# SCH_ESP-CellCore_USB_Interlock_RevA3_2.net
KiCad netlist of a schematic drawn in EasyEDA
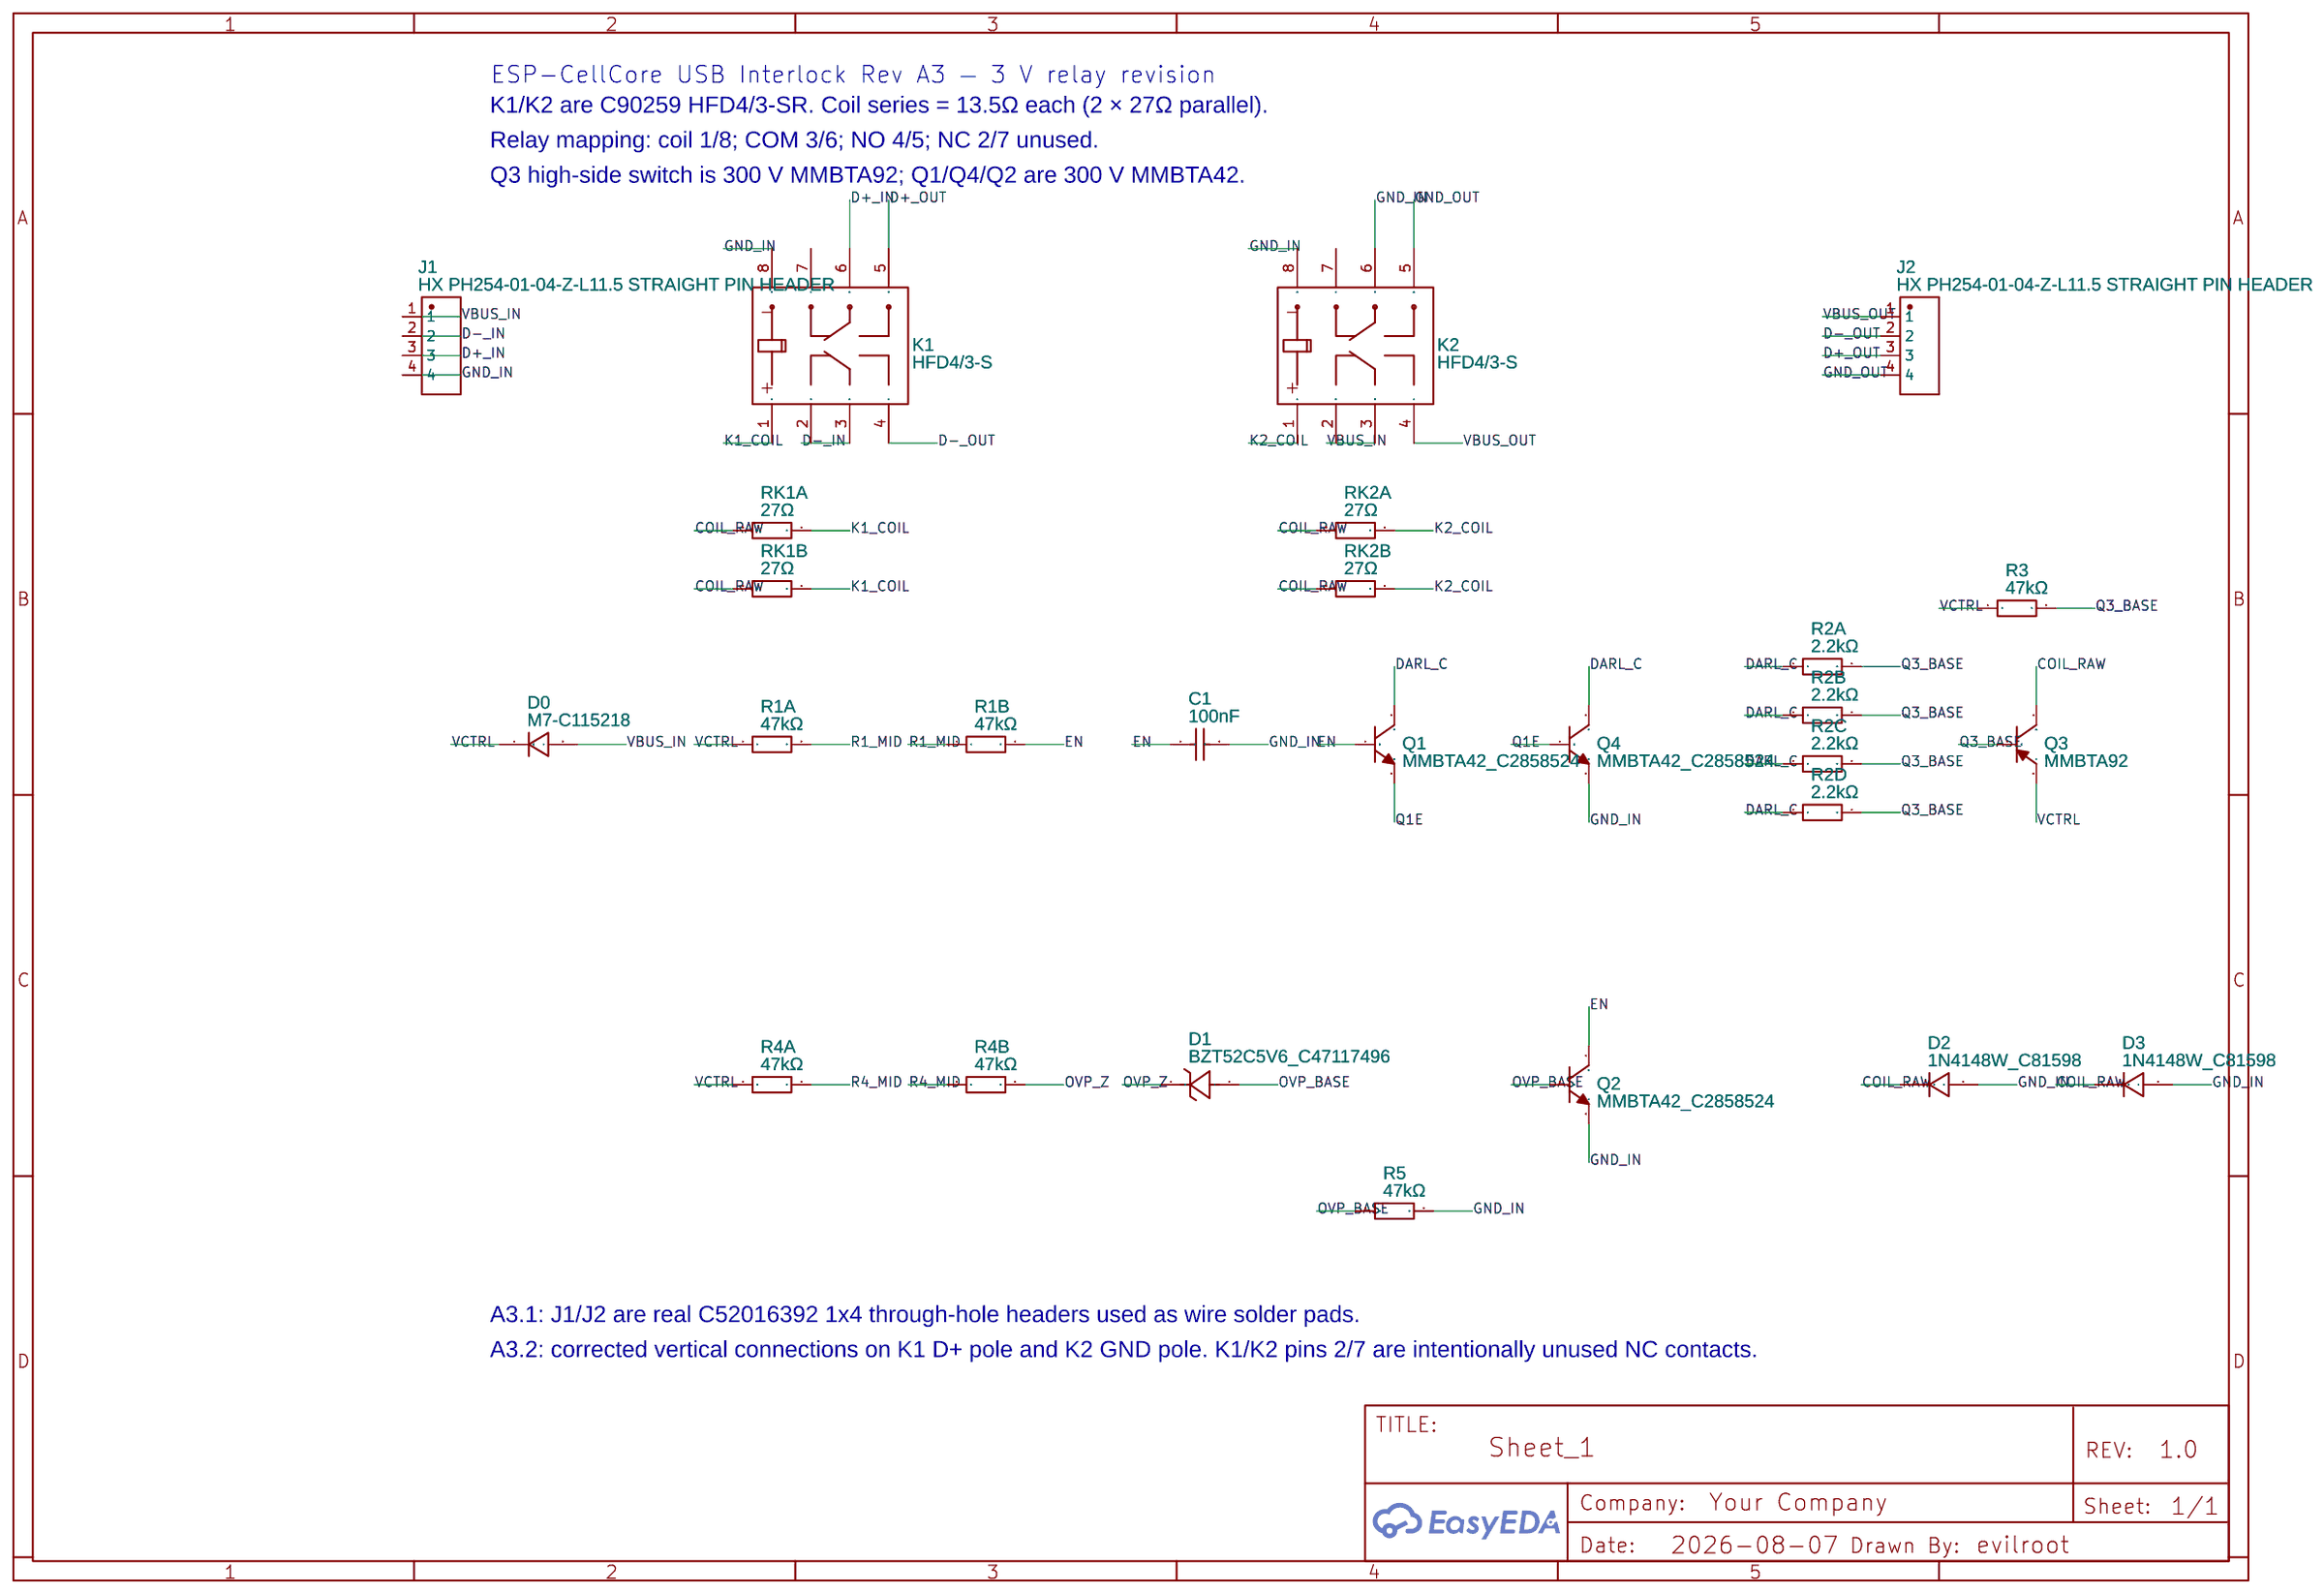
[diagram p0: schematic sheet]

(export (version "E")
  (design (tool "Eeschema 10.0.6"))
  (components
    (comp (ref "C1")
      (value "100nF")
      (fields
        (field (name "Manufacturer Part") "C0805C104K5RAC7800")
        (field (name "Manufacturer") "KEMET(基美)")
      )
      (libsource (lib "") (part "C0805C104K5RACTU"))
    )
    (comp (ref "D0")
      (value "M7-C115218")
      (fields (field (name "Manufacturer Part") "M7") (field (name "Manufacturer") "晶导微电子"))
      (libsource (lib "") (part "M7-C115218"))
    )
    (comp (ref "D1")
      (value "BZT52C5V6_C47117496")
      (fields (field (name "Manufacturer Part") "BZT52C5V6") (field (name "Manufacturer") "baocheng(宝乘)"))
      (libsource (lib "") (part "BZT52C5V6_C47117496"))
    )
    (comp (ref "D2")
      (value "1N4148W_C81598")
      (fields (field (name "Manufacturer Part") "1N4148W") (field (name "Manufacturer") "ST(先科)"))
      (libsource (lib "") (part "1N4148W_C81598"))
    )
    (comp (ref "D3")
      (value "1N4148W_C81598")
      (fields (field (name "Manufacturer Part") "1N4148W") (field (name "Manufacturer") "ST(先科)"))
      (libsource (lib "") (part "1N4148W_C81598"))
    )
    (comp (ref "J1")
      (value "HX PH254-01-04-Z-L11.5 STRAIGHT PIN HEADER")
      (fields
        (field (name "Manufacturer Part") "HX PH254-01-04-Z-L11.5 straight pin header")
        (field (name "Manufacturer") "hanxia(韩下)")
      )
      (libsource (lib "") (part "HX PH254-01-04-Z-L11.5 STRAIGHT PIN HEADER"))
    )
    (comp (ref "J2")
      (value "HX PH254-01-04-Z-L11.5 STRAIGHT PIN HEADER")
      (fields
        (field (name "Manufacturer Part") "HX PH254-01-04-Z-L11.5 straight pin header")
        (field (name "Manufacturer") "hanxia(韩下)")
      )
      (libsource (lib "") (part "HX PH254-01-04-Z-L11.5 STRAIGHT PIN HEADER"))
    )
    (comp (ref "K1")
      (value "HFD4/3-S")
      (fields (field (name "Manufacturer Part") "HFD4/3-SR") (field (name "Manufacturer") "HF(宏发)"))
      (libsource (lib "") (part "HFD4/3-S"))
    )
    (comp (ref "K2")
      (value "HFD4/3-S")
      (fields (field (name "Manufacturer Part") "HFD4/3-SR") (field (name "Manufacturer") "HF(宏发)"))
      (libsource (lib "") (part "HFD4/3-S"))
    )
    (comp (ref "Q1")
      (value "MMBTA42_C2858524")
      (fields (field (name "Manufacturer Part") "MMBTA42") (field (name "Manufacturer") "MDD(辰达半导体)"))
      (libsource (lib "") (part "MMBTA42_C2858524"))
    )
    (comp (ref "Q2")
      (value "MMBTA42_C2858524")
      (fields (field (name "Manufacturer Part") "MMBTA42") (field (name "Manufacturer") "MDD(辰达半导体)"))
      (libsource (lib "") (part "MMBTA42_C2858524"))
    )
    (comp (ref "Q3")
      (value "MMBTA92")
      (fields (field (name "Manufacturer") "GOODWORK(固得沃克)"))
      (libsource (lib "") (part "MMBTA92"))
    )
    (comp (ref "Q4")
      (value "MMBTA42_C2858524")
      (fields (field (name "Manufacturer Part") "MMBTA42") (field (name "Manufacturer") "MDD(辰达半导体)"))
      (libsource (lib "") (part "MMBTA42_C2858524"))
    )
    (comp (ref "R1A")
      (value "47kΩ")
      (fields (field (name "Manufacturer Part") "AC0805FR-0747KL") (field (name "Manufacturer") "YAGEO(国巨)"))
      (libsource (lib "") (part "AC0805FR-0747KL_4"))
    )
    (comp (ref "R1B")
      (value "47kΩ")
      (fields (field (name "Manufacturer Part") "AC0805FR-0747KL") (field (name "Manufacturer") "YAGEO(国巨)"))
      (libsource (lib "") (part "AC0805FR-0747KL"))
    )
    (comp (ref "R2A")
      (value "2.2kΩ")
      (fields
        (field (name "Manufacturer Part") "0805W8F2201T5E")
        (field (name "Manufacturer") "UNI-ROYAL(厚声)")
      )
      (libsource (lib "") (part "0805W8F2201T5E_3"))
    )
    (comp (ref "R2B")
      (value "2.2kΩ")
      (fields
        (field (name "Manufacturer Part") "0805W8F2201T5E")
        (field (name "Manufacturer") "UNI-ROYAL(厚声)")
      )
      (libsource (lib "") (part "0805W8F2201T5E_1"))
    )
    (comp (ref "R2C")
      (value "2.2kΩ")
      (fields
        (field (name "Manufacturer Part") "0805W8F2201T5E")
        (field (name "Manufacturer") "UNI-ROYAL(厚声)")
      )
      (libsource (lib "") (part "0805W8F2201T5E"))
    )
    (comp (ref "R2D")
      (value "2.2kΩ")
      (fields
        (field (name "Manufacturer Part") "0805W8F2201T5E")
        (field (name "Manufacturer") "UNI-ROYAL(厚声)")
      )
      (libsource (lib "") (part "0805W8F2201T5E_2"))
    )
    (comp (ref "R3")
      (value "47kΩ")
      (fields (field (name "Manufacturer Part") "AC0805FR-0747KL") (field (name "Manufacturer") "YAGEO(国巨)"))
      (libsource (lib "") (part "AC0805FR-0747KL_2"))
    )
    (comp (ref "R4A")
      (value "47kΩ")
      (fields (field (name "Manufacturer Part") "AC0805FR-0747KL") (field (name "Manufacturer") "YAGEO(国巨)"))
      (libsource (lib "") (part "AC0805FR-0747KL_3"))
    )
    (comp (ref "R4B")
      (value "47kΩ")
      (fields (field (name "Manufacturer Part") "AC0805FR-0747KL") (field (name "Manufacturer") "YAGEO(国巨)"))
      (libsource (lib "") (part "AC0805FR-0747KL_1"))
    )
    (comp (ref "R5")
      (value "47kΩ")
      (fields (field (name "Manufacturer Part") "AC0805FR-0747KL") (field (name "Manufacturer") "YAGEO(国巨)"))
      (libsource (lib "") (part "AC0805FR-0747KL_2"))
    )
    (comp (ref "RK1A")
      (value "27Ω")
      (fields (field (name "Manufacturer Part") "CR0805F827R0G") (field (name "Manufacturer") "LIZ(丽智电子)"))
      (libsource (lib "") (part "CR0805F827R0G_1"))
    )
    (comp (ref "RK1B")
      (value "27Ω")
      (fields (field (name "Manufacturer Part") "CR0805F827R0G") (field (name "Manufacturer") "LIZ(丽智电子)"))
      (libsource (lib "") (part "CR0805F827R0G_3"))
    )
    (comp (ref "RK2A")
      (value "27Ω")
      (fields (field (name "Manufacturer Part") "CR0805F827R0G") (field (name "Manufacturer") "LIZ(丽智电子)"))
      (libsource (lib "") (part "CR0805F827R0G_2"))
    )
    (comp (ref "RK2B")
      (value "27Ω")
      (fields (field (name "Manufacturer Part") "CR0805F827R0G") (field (name "Manufacturer") "LIZ(丽智电子)"))
      (libsource (lib "") (part "CR0805F827R0G"))
    )
  )
  (nets
    (net (code "1") (name "/COIL_RAW") (class "Default")
      (node (ref "D2") (pin "1") (pinfunction "K_1") (pintype "unspecified"))
      (node (ref "D3") (pin "1") (pinfunction "K_1") (pintype "unspecified"))
      (node (ref "Q3") (pin "3") (pinfunction "C_3") (pintype "input"))
      (node (ref "RK1A") (pin "1") (pinfunction "1_1") (pintype "input"))
      (node (ref "RK1B") (pin "1") (pinfunction "1_1") (pintype "input"))
      (node (ref "RK2A") (pin "1") (pinfunction "1_1") (pintype "input"))
      (node (ref "RK2B") (pin "1") (pinfunction "1_1") (pintype "input"))
    )
    (net (code "2") (name "/D+_IN") (class "Default")
      (node (ref "J1") (pin "3") (pinfunction "3_3") (pintype "unspecified"))
      (node (ref "K1") (pin "6") (pinfunction "6_6") (pintype "input"))
    )
    (net (code "3") (name "/D+_OUT") (class "Default")
      (node (ref "J2") (pin "3") (pinfunction "3_3") (pintype "unspecified"))
      (node (ref "K1") (pin "5") (pinfunction "5_5") (pintype "input"))
    )
    (net (code "4") (name "/D-_IN") (class "Default")
      (node (ref "J1") (pin "2") (pinfunction "2_2") (pintype "unspecified"))
      (node (ref "K1") (pin "3") (pinfunction "3_3") (pintype "input"))
    )
    (net (code "5") (name "/D-_OUT") (class "Default")
      (node (ref "J2") (pin "2") (pinfunction "2_2") (pintype "unspecified"))
      (node (ref "K1") (pin "4") (pinfunction "4_4") (pintype "input"))
    )
    (net (code "6") (name "/DARL_C") (class "Default")
      (node (ref "Q1") (pin "3") (pinfunction "C_3") (pintype "input"))
      (node (ref "Q4") (pin "3") (pinfunction "C_3") (pintype "input"))
      (node (ref "R2A") (pin "1") (pinfunction "1_1") (pintype "input"))
      (node (ref "R2B") (pin "1") (pinfunction "1_1") (pintype "input"))
      (node (ref "R2C") (pin "1") (pinfunction "1_1") (pintype "input"))
      (node (ref "R2D") (pin "1") (pinfunction "1_1") (pintype "input"))
    )
    (net (code "7") (name "/EN") (class "Default")
      (node (ref "C1") (pin "1") (pinfunction "1_1") (pintype "input"))
      (node (ref "Q1") (pin "1") (pinfunction "B_1") (pintype "input"))
      (node (ref "Q2") (pin "3") (pinfunction "C_3") (pintype "input"))
      (node (ref "R1B") (pin "2") (pinfunction "2_2") (pintype "unspecified"))
    )
    (net (code "8") (name "/GND_IN") (class "Default")
      (node (ref "C1") (pin "2") (pinfunction "2_2") (pintype "input"))
      (node (ref "D2") (pin "2") (pinfunction "A_2") (pintype "unspecified"))
      (node (ref "D3") (pin "2") (pinfunction "A_2") (pintype "unspecified"))
      (node (ref "J1") (pin "4") (pinfunction "4_4") (pintype "unspecified"))
      (node (ref "K1") (pin "8") (pinfunction "8_8") (pintype "input"))
      (node (ref "K2") (pin "6") (pinfunction "6_6") (pintype "input"))
      (node (ref "K2") (pin "8") (pinfunction "8_8") (pintype "input"))
      (node (ref "Q2") (pin "2") (pinfunction "E_2") (pintype "input"))
      (node (ref "Q4") (pin "2") (pinfunction "E_2") (pintype "input"))
      (node (ref "R5") (pin "2") (pinfunction "2_2") (pintype "unspecified"))
    )
    (net (code "9") (name "/GND_OUT") (class "Default")
      (node (ref "J2") (pin "4") (pinfunction "4_4") (pintype "unspecified"))
      (node (ref "K2") (pin "5") (pinfunction "5_5") (pintype "input"))
    )
    (net (code "10") (name "/K1_COIL") (class "Default")
      (node (ref "K1") (pin "1") (pinfunction "1_1") (pintype "input"))
      (node (ref "RK1A") (pin "2") (pinfunction "2_2") (pintype "input"))
      (node (ref "RK1B") (pin "2") (pinfunction "2_2") (pintype "input"))
    )
    (net (code "11") (name "/K2_COIL") (class "Default")
      (node (ref "K2") (pin "1") (pinfunction "1_1") (pintype "input"))
      (node (ref "RK2A") (pin "2") (pinfunction "2_2") (pintype "input"))
      (node (ref "RK2B") (pin "2") (pinfunction "2_2") (pintype "input"))
    )
    (net (code "12") (name "/OVP_BASE") (class "Default")
      (node (ref "D1") (pin "2") (pinfunction "A_2") (pintype "unspecified"))
      (node (ref "Q2") (pin "1") (pinfunction "B_1") (pintype "input"))
      (node (ref "R5") (pin "1") (pinfunction "1_1") (pintype "unspecified"))
    )
    (net (code "13") (name "/OVP_Z") (class "Default")
      (node (ref "D1") (pin "1") (pinfunction "C_1") (pintype "unspecified"))
      (node (ref "R4B") (pin "2") (pinfunction "2_2") (pintype "unspecified"))
    )
    (net (code "14") (name "/Q1E") (class "Default")
      (node (ref "Q1") (pin "2") (pinfunction "E_2") (pintype "input"))
      (node (ref "Q4") (pin "1") (pinfunction "B_1") (pintype "input"))
    )
    (net (code "15") (name "/Q3_BASE") (class "Default")
      (node (ref "Q3") (pin "1") (pinfunction "B_1") (pintype "input"))
      (node (ref "R2A") (pin "2") (pinfunction "2_2") (pintype "input"))
      (node (ref "R2B") (pin "2") (pinfunction "2_2") (pintype "input"))
      (node (ref "R2C") (pin "2") (pinfunction "2_2") (pintype "input"))
      (node (ref "R2D") (pin "2") (pinfunction "2_2") (pintype "input"))
      (node (ref "R3") (pin "2") (pinfunction "2_2") (pintype "unspecified"))
    )
    (net (code "16") (name "/R1_MID") (class "Default")
      (node (ref "R1A") (pin "2") (pinfunction "2_2") (pintype "unspecified"))
      (node (ref "R1B") (pin "1") (pinfunction "1_1") (pintype "unspecified"))
    )
    (net (code "17") (name "/R4_MID") (class "Default")
      (node (ref "R4A") (pin "2") (pinfunction "2_2") (pintype "unspecified"))
      (node (ref "R4B") (pin "1") (pinfunction "1_1") (pintype "unspecified"))
    )
    (net (code "18") (name "/VBUS_IN") (class "Default")
      (node (ref "D0") (pin "2") (pinfunction "A_2") (pintype "unspecified"))
      (node (ref "J1") (pin "1") (pinfunction "1_1") (pintype "unspecified"))
      (node (ref "K2") (pin "3") (pinfunction "3_3") (pintype "input"))
    )
    (net (code "19") (name "/VBUS_OUT") (class "Default")
      (node (ref "J2") (pin "1") (pinfunction "1_1") (pintype "unspecified"))
      (node (ref "K2") (pin "4") (pinfunction "4_4") (pintype "input"))
    )
    (net (code "20") (name "/VCTRL") (class "Default")
      (node (ref "D0") (pin "1") (pinfunction "C_1") (pintype "unspecified"))
      (node (ref "Q3") (pin "2") (pinfunction "E_2") (pintype "input"))
      (node (ref "R1A") (pin "1") (pinfunction "1_1") (pintype "unspecified"))
      (node (ref "R3") (pin "1") (pinfunction "1_1") (pintype "unspecified"))
      (node (ref "R4A") (pin "1") (pinfunction "1_1") (pintype "unspecified"))
    )
    (net (code "21") (name "unconnected-(K1-Pad2)") (class "Default")
      (node (ref "K1") (pin "2") (pinfunction "2_2") (pintype "input"))
    )
    (net (code "22") (name "unconnected-(K1-Pad7)") (class "Default")
      (node (ref "K1") (pin "7") (pinfunction "7_7") (pintype "input"))
    )
    (net (code "23") (name "unconnected-(K2-Pad2)") (class "Default")
      (node (ref "K2") (pin "2") (pinfunction "2_2") (pintype "input"))
    )
    (net (code "24") (name "unconnected-(K2-Pad7)") (class "Default")
      (node (ref "K2") (pin "7") (pinfunction "7_7") (pintype "input"))
    )
  )
)
